# ESP.net
KiCad netlist of a schematic drawn in Altium Designer
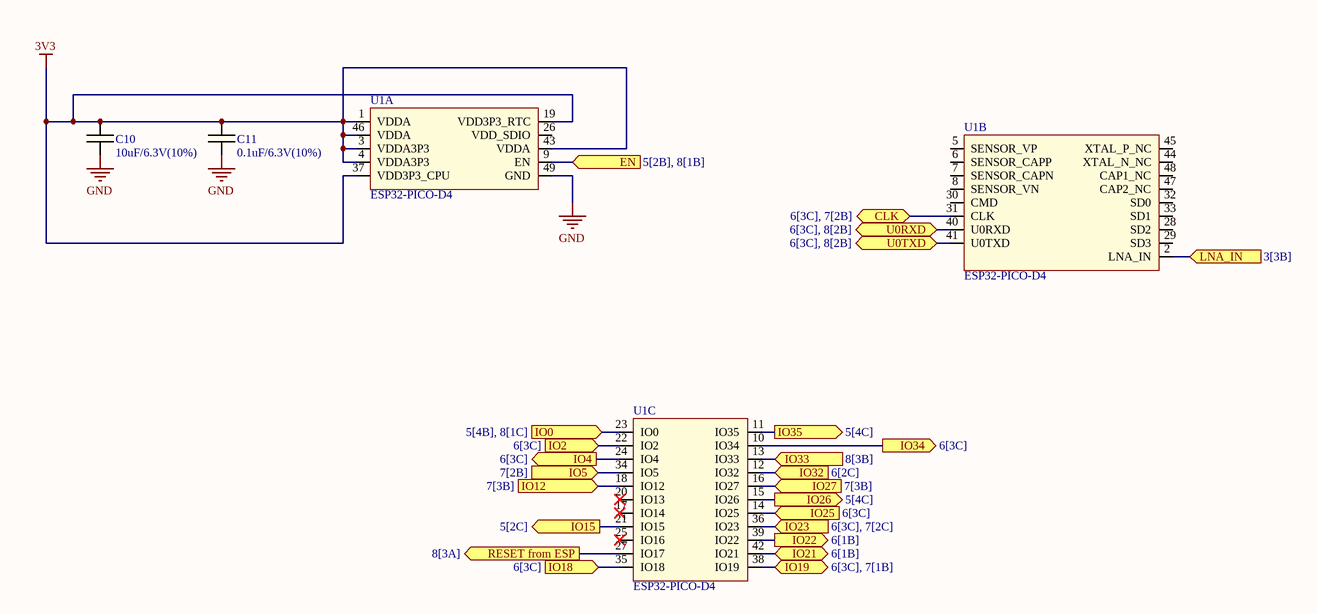
[diagram p0: ESP.SchDoc]

(export (version "E")
  (design (tool "Eeschema 10.0.6"))
  (components
    (comp (ref "C10")
      (value "10uF/6.3V(10%)")
      (footprint "CAPC1005X06N")
      (libsource (lib "SCHLibrary") (part "Capacitor"))
    )
    (comp (ref "C11")
      (value "0.1uF/6.3V(10%)")
      (footprint "CAPC1005X06N")
      (libsource (lib "SCHLibrary") (part "Capacitor"))
    )
    (comp (ref "U1")
      (value "ESP32-PICO-D4")
      (footprint "PQFN50P700X700X104_HS-49N")
      (libsource (lib "SCHLibrary") (part "ESP32"))
    )
  )
  (nets
    (net (code "1") (name "/CLK") (class "Default")
      (node (ref "U1") (pin "31") (pinfunction "CLK_31") (pintype "passive"))
    )
    (net (code "2") (name "/EN") (class "Default")
      (node (ref "U1") (pin "9") (pinfunction "EN_9") (pintype "passive"))
    )
    (net (code "3") (name "/IO0") (class "Default")
      (node (ref "U1") (pin "23") (pinfunction "IO0_23") (pintype "passive"))
    )
    (net (code "4") (name "/IO2") (class "Default")
      (node (ref "U1") (pin "22") (pinfunction "IO2_22") (pintype "passive"))
    )
    (net (code "5") (name "/IO4") (class "Default")
      (node (ref "U1") (pin "24") (pinfunction "IO4_24") (pintype "passive"))
    )
    (net (code "6") (name "/IO5") (class "Default")
      (node (ref "U1") (pin "34") (pinfunction "IO5_34") (pintype "passive"))
    )
    (net (code "7") (name "/IO12") (class "Default")
      (node (ref "U1") (pin "18") (pinfunction "IO12_18") (pintype "passive"))
    )
    (net (code "8") (name "/IO15") (class "Default")
      (node (ref "U1") (pin "21") (pinfunction "IO15_21") (pintype "passive"))
    )
    (net (code "9") (name "/IO18") (class "Default")
      (node (ref "U1") (pin "35") (pinfunction "IO18_35") (pintype "passive"))
    )
    (net (code "10") (name "/IO19") (class "Default")
      (node (ref "U1") (pin "38") (pinfunction "IO19_38") (pintype "passive"))
    )
    (net (code "11") (name "/IO21") (class "Default")
      (node (ref "U1") (pin "42") (pinfunction "IO21_42") (pintype "passive"))
    )
    (net (code "12") (name "/IO22") (class "Default")
      (node (ref "U1") (pin "39") (pinfunction "IO22_39") (pintype "passive"))
    )
    (net (code "13") (name "/IO23") (class "Default")
      (node (ref "U1") (pin "36") (pinfunction "IO23_36") (pintype "passive"))
    )
    (net (code "14") (name "/IO25") (class "Default")
      (node (ref "U1") (pin "14") (pinfunction "IO25_14") (pintype "passive"))
    )
    (net (code "15") (name "/IO26") (class "Default")
      (node (ref "U1") (pin "15") (pinfunction "IO26_15") (pintype "passive"))
    )
    (net (code "16") (name "/IO27") (class "Default")
      (node (ref "U1") (pin "16") (pinfunction "IO27_16") (pintype "passive"))
    )
    (net (code "17") (name "/IO32") (class "Default")
      (node (ref "U1") (pin "12") (pinfunction "IO32_12") (pintype "passive"))
    )
    (net (code "18") (name "/IO33") (class "Default")
      (node (ref "U1") (pin "13") (pinfunction "IO33_13") (pintype "passive"))
    )
    (net (code "19") (name "/IO34") (class "Default")
      (node (ref "U1") (pin "10") (pinfunction "IO34_10") (pintype "passive"))
    )
    (net (code "20") (name "/IO35") (class "Default")
      (node (ref "U1") (pin "11") (pinfunction "IO35_11") (pintype "passive"))
    )
    (net (code "21") (name "/LNA_IN") (class "Default")
      (node (ref "U1") (pin "2") (pinfunction "LNA_IN_2") (pintype "passive"))
    )
    (net (code "22") (name "/RESET from ESP") (class "Default")
      (node (ref "U1") (pin "27") (pinfunction "IO17_27") (pintype "passive"))
    )
    (net (code "23") (name "/U0RXD") (class "Default")
      (node (ref "U1") (pin "40") (pinfunction "U0RXD_40") (pintype "passive"))
    )
    (net (code "24") (name "/U0TXD") (class "Default")
      (node (ref "U1") (pin "41") (pinfunction "U0TXD_41") (pintype "passive"))
    )
    (net (code "25") (name "3V3") (class "Default")
      (node (ref "C10") (pin "2") (pinfunction "2_2") (pintype "passive"))
      (node (ref "C11") (pin "2") (pinfunction "2_2") (pintype "passive"))
      (node (ref "U1") (pin "1") (pinfunction "VDDA_1") (pintype "passive"))
      (node (ref "U1") (pin "19") (pinfunction "VDD3P3_RTC_19") (pintype "passive"))
      (node (ref "U1") (pin "3") (pinfunction "VDDA3P3_3") (pintype "passive"))
      (node (ref "U1") (pin "37") (pinfunction "VDD3P3_CPU_37") (pintype "passive"))
      (node (ref "U1") (pin "4") (pinfunction "VDDA3P3_4") (pintype "passive"))
      (node (ref "U1") (pin "43") (pinfunction "VDDA_43") (pintype "passive"))
      (node (ref "U1") (pin "46") (pinfunction "VDDA_46") (pintype "passive"))
    )
    (net (code "26") (name "GND") (class "Default")
      (node (ref "C10") (pin "1") (pinfunction "1_1") (pintype "passive"))
      (node (ref "C11") (pin "1") (pinfunction "1_1") (pintype "passive"))
      (node (ref "U1") (pin "49") (pinfunction "GND_49") (pintype "passive"))
    )
    (net (code "27") (name "unconnected-(U1A-VDD_SDIO-Pad26)") (class "Default")
      (node (ref "U1") (pin "26") (pinfunction "VDD_SDIO_26") (pintype "passive"))
    )
    (net (code "28") (name "unconnected-(U1B-CAP1_NC-Pad48)") (class "Default")
      (node (ref "U1") (pin "48") (pinfunction "CAP1_NC_48") (pintype "passive"))
    )
    (net (code "29") (name "unconnected-(U1B-CAP2_NC-Pad47)") (class "Default")
      (node (ref "U1") (pin "47") (pinfunction "CAP2_NC_47") (pintype "passive"))
    )
    (net (code "30") (name "unconnected-(U1B-CMD-Pad30)") (class "Default")
      (node (ref "U1") (pin "30") (pinfunction "CMD_30") (pintype "passive"))
    )
    (net (code "31") (name "unconnected-(U1B-SD0-Pad32)") (class "Default")
      (node (ref "U1") (pin "32") (pinfunction "SD0_32") (pintype "passive"))
    )
    (net (code "32") (name "unconnected-(U1B-SD1-Pad33)") (class "Default")
      (node (ref "U1") (pin "33") (pinfunction "SD1_33") (pintype "passive"))
    )
    (net (code "33") (name "unconnected-(U1B-SD2-Pad28)") (class "Default")
      (node (ref "U1") (pin "28") (pinfunction "SD2_28") (pintype "passive"))
    )
    (net (code "34") (name "unconnected-(U1B-SD3-Pad29)") (class "Default")
      (node (ref "U1") (pin "29") (pinfunction "SD3_29") (pintype "passive"))
    )
    (net (code "35") (name "unconnected-(U1B-SENSOR_CAPN-Pad7)") (class "Default")
      (node (ref "U1") (pin "7") (pinfunction "SENSOR_CAPN_7") (pintype "passive"))
    )
    (net (code "36") (name "unconnected-(U1B-SENSOR_CAPP-Pad6)") (class "Default")
      (node (ref "U1") (pin "6") (pinfunction "SENSOR_CAPP_6") (pintype "passive"))
    )
    (net (code "37") (name "unconnected-(U1B-SENSOR_VN-Pad8)") (class "Default")
      (node (ref "U1") (pin "8") (pinfunction "SENSOR_VN_8") (pintype "passive"))
    )
    (net (code "38") (name "unconnected-(U1B-SENSOR_VP-Pad5)") (class "Default")
      (node (ref "U1") (pin "5") (pinfunction "SENSOR_VP_5") (pintype "passive"))
    )
    (net (code "39") (name "unconnected-(U1B-XTAL_N_NC-Pad44)") (class "Default")
      (node (ref "U1") (pin "44") (pinfunction "XTAL_N_NC_44") (pintype "passive"))
    )
    (net (code "40") (name "unconnected-(U1B-XTAL_P_NC-Pad45)") (class "Default")
      (node (ref "U1") (pin "45") (pinfunction "XTAL_P_NC_45") (pintype "passive"))
    )
    (net (code "41") (name "unconnected-(U1C-IO13-Pad20)") (class "Default")
      (node (ref "U1") (pin "20") (pinfunction "IO13_20") (pintype "passive+no_connect"))
    )
    (net (code "42") (name "unconnected-(U1C-IO14-Pad17)") (class "Default")
      (node (ref "U1") (pin "17") (pinfunction "IO14_17") (pintype "passive+no_connect"))
    )
    (net (code "43") (name "unconnected-(U1C-IO16-Pad25)") (class "Default")
      (node (ref "U1") (pin "25") (pinfunction "IO16_25") (pintype "passive+no_connect"))
    )
  )
)
